# HKCV5.net
KiCad netlist of a schematic drawn in EAGLE
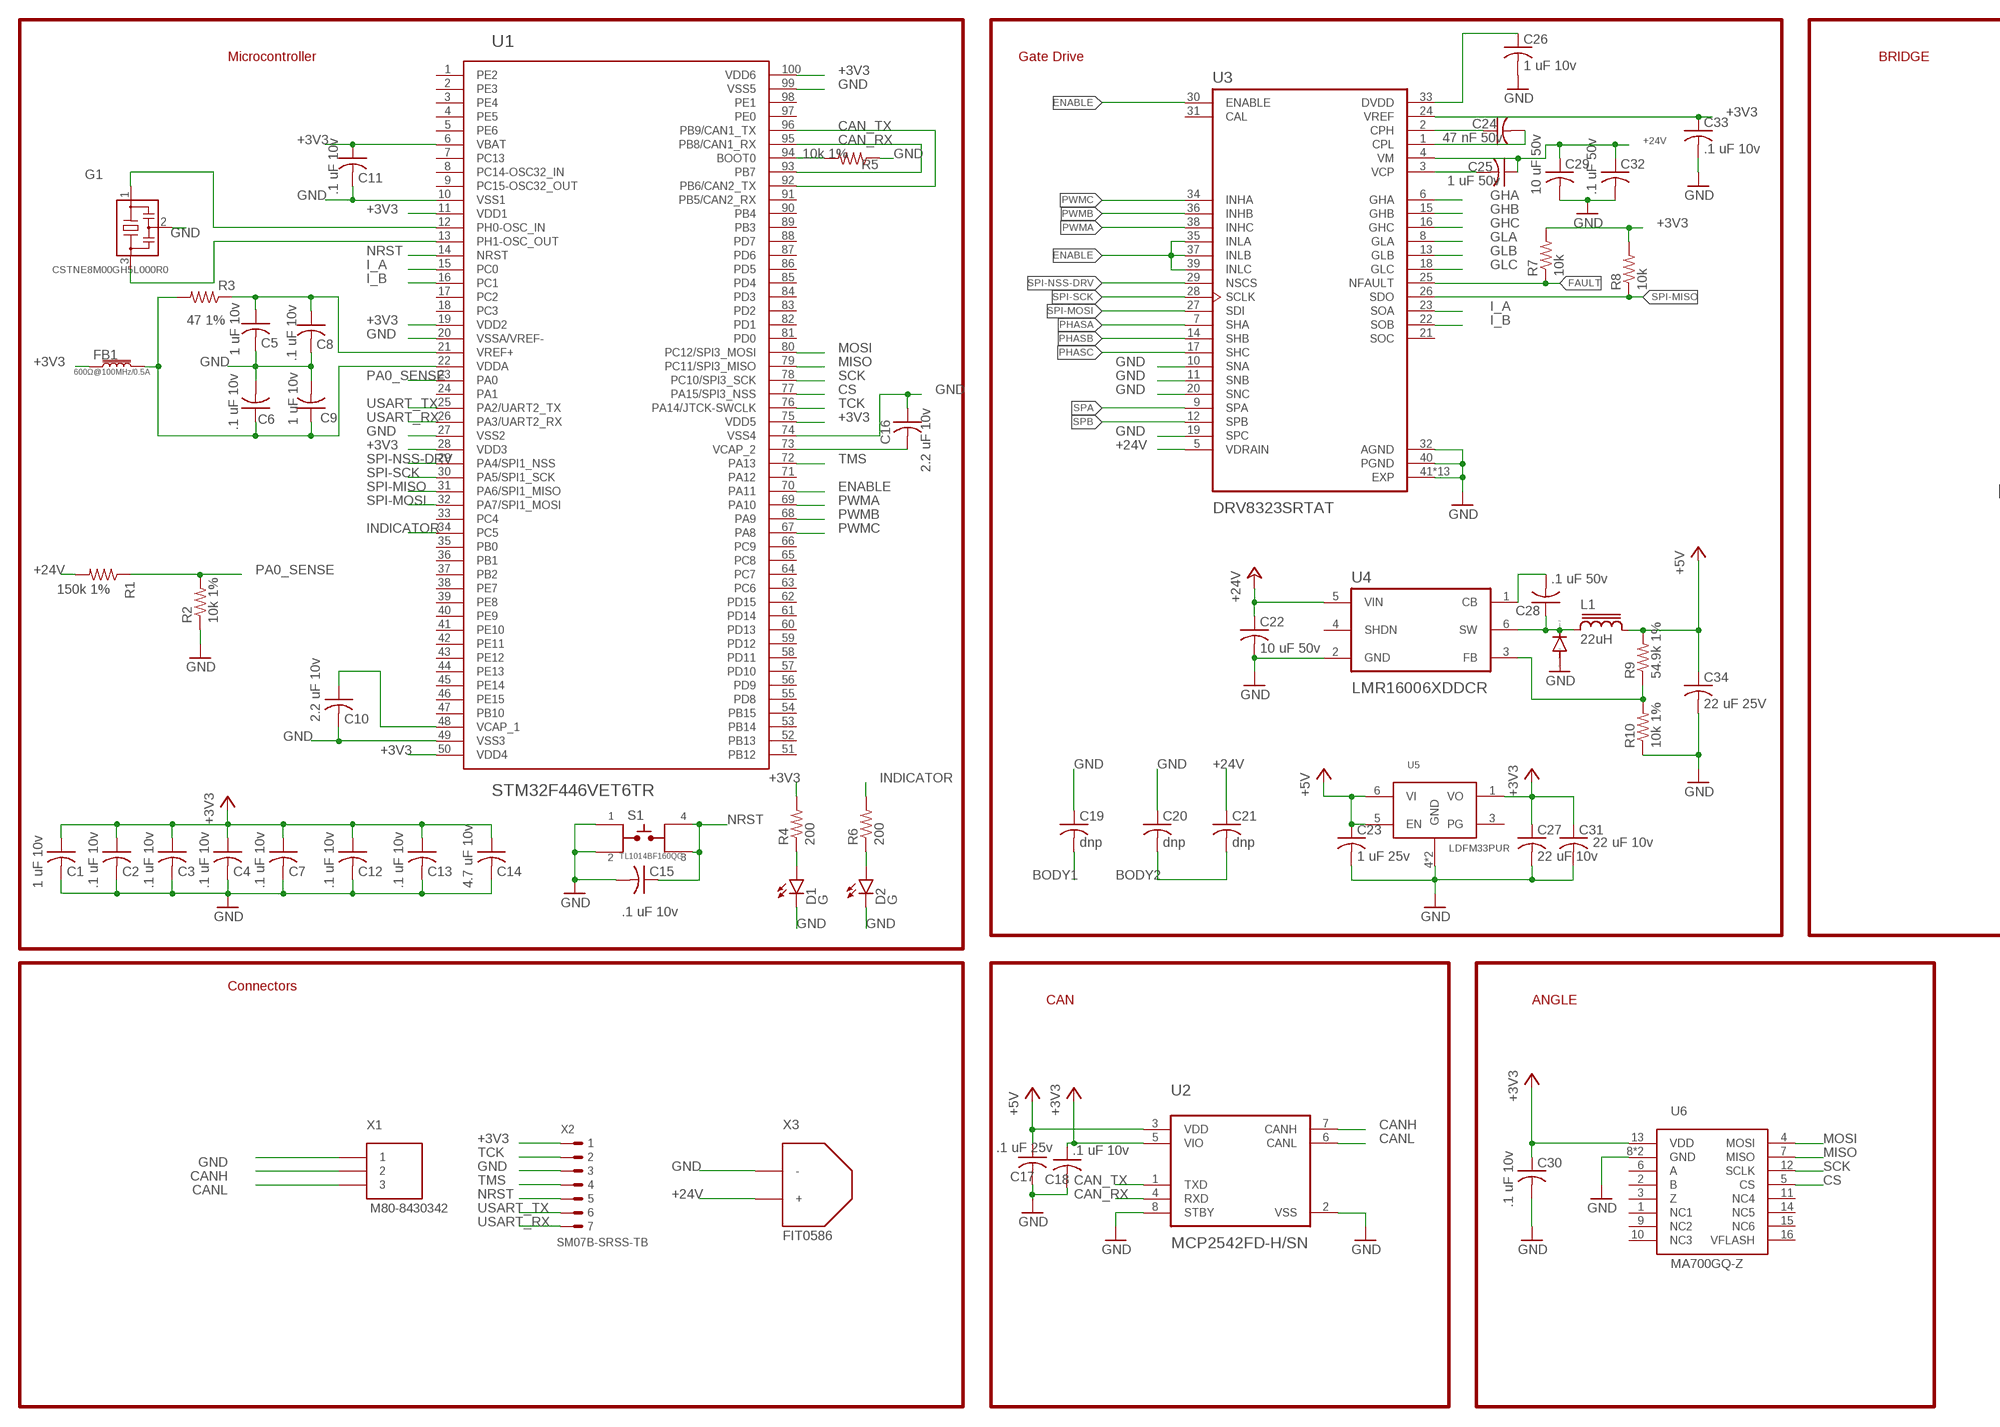
[diagram p0: schematic, sheet 1, part 1 of 2]
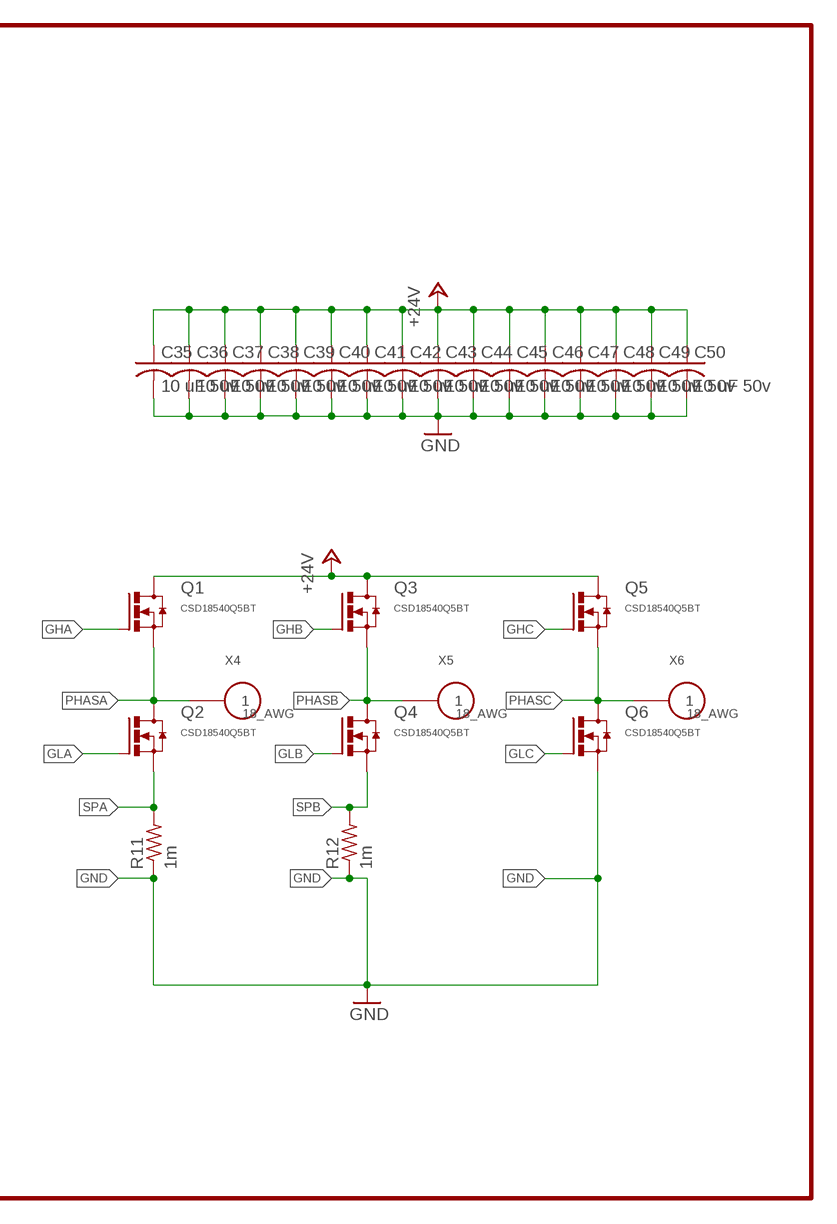
[diagram p1: schematic, sheet 1, part 2 of 2]

(export (version "E")
  (design (tool "Eeschema 10.0.6"))
  (components
    (comp (ref "C1")
      (value "1 uF 10v")
      (footprint "eagle-import:C0402K")
      (libsource (lib "eagle-import") (part "C-USC0402K"))
    )
    (comp (ref "C2")
      (value ".1 uF 10v")
      (footprint "eagle-import:C0402K")
      (libsource (lib "eagle-import") (part "C-USC0402K"))
    )
    (comp (ref "C3")
      (value ".1 uF 10v")
      (footprint "eagle-import:C0402K")
      (libsource (lib "eagle-import") (part "C-USC0402K"))
    )
    (comp (ref "C4")
      (value ".1 uF 10v")
      (footprint "eagle-import:C0402K")
      (libsource (lib "eagle-import") (part "C-USC0402K"))
    )
    (comp (ref "C5")
      (value "1 uF 10v")
      (footprint "eagle-import:C0402K")
      (libsource (lib "eagle-import") (part "C-USC0402K"))
    )
    (comp (ref "C6")
      (value ".1 uF 10v")
      (footprint "eagle-import:C0402K")
      (libsource (lib "eagle-import") (part "C-USC0402K"))
    )
    (comp (ref "C7")
      (value ".1 uF 10v")
      (footprint "eagle-import:C0402K")
      (libsource (lib "eagle-import") (part "C-USC0402K"))
    )
    (comp (ref "C8")
      (value ".1 uF 10v")
      (footprint "eagle-import:C0402K")
      (libsource (lib "eagle-import") (part "C-USC0402K"))
    )
    (comp (ref "C9")
      (value "1 uF 10v")
      (footprint "eagle-import:C0402K")
      (libsource (lib "eagle-import") (part "C-USC0402K"))
    )
    (comp (ref "C10")
      (value "2.2 uF 10v")
      (footprint "eagle-import:C0402K")
      (libsource (lib "eagle-import") (part "C-USC0402K"))
    )
    (comp (ref "C11")
      (value ".1 uF 10v")
      (footprint "eagle-import:C0402K")
      (libsource (lib "eagle-import") (part "C-USC0402K"))
    )
    (comp (ref "C12")
      (value ".1 uF 10v")
      (footprint "eagle-import:C0402K")
      (libsource (lib "eagle-import") (part "C-USC0402K"))
    )
    (comp (ref "C13")
      (value ".1 uF 10v")
      (footprint "eagle-import:C0402K")
      (libsource (lib "eagle-import") (part "C-USC0402K"))
    )
    (comp (ref "C14")
      (value "4.7 uF 10v")
      (footprint "eagle-import:C0402K")
      (libsource (lib "eagle-import") (part "C-USC0402K"))
    )
    (comp (ref "C15")
      (value ".1 uF 10v")
      (footprint "eagle-import:C0402K")
      (libsource (lib "eagle-import") (part "C-USC0402K"))
    )
    (comp (ref "C16")
      (value "2.2 uF 10v")
      (footprint "eagle-import:C0402K")
      (libsource (lib "eagle-import") (part "C-USC0402K"))
    )
    (comp (ref "C17")
      (value ".1 uF 25v")
      (footprint "eagle-import:C0402K")
      (libsource (lib "eagle-import") (part "C-USC0402K"))
    )
    (comp (ref "C18")
      (value ".1 uF 10v")
      (footprint "eagle-import:C0402K")
      (libsource (lib "eagle-import") (part "C-USC0402K"))
    )
    (comp (ref "C19")
      (value "dnp")
      (footprint "eagle-import:C0402K")
      (libsource (lib "eagle-import") (part "C-USC0402K"))
    )
    (comp (ref "C20")
      (value "dnp")
      (footprint "eagle-import:C0402K")
      (libsource (lib "eagle-import") (part "C-USC0402K"))
    )
    (comp (ref "C21")
      (value "dnp")
      (footprint "eagle-import:C0402K")
      (libsource (lib "eagle-import") (part "C-USC0402K"))
    )
    (comp (ref "C22")
      (value "10 uF 50v")
      (footprint "eagle-import:C1206K")
      (libsource (lib "eagle-import") (part "C-USC1206K"))
    )
    (comp (ref "C23")
      (value "1 uF 25v")
      (footprint "eagle-import:C0402K")
      (libsource (lib "eagle-import") (part "C-USC0402K"))
    )
    (comp (ref "C24")
      (value "47 nF 50v")
      (footprint "eagle-import:C0402K")
      (libsource (lib "eagle-import") (part "C-USC0402K"))
    )
    (comp (ref "C25")
      (value "1 uF 50v")
      (footprint "eagle-import:C0603K")
      (libsource (lib "eagle-import") (part "C-USC0603K"))
    )
    (comp (ref "C26")
      (value "1 uF 10v")
      (footprint "eagle-import:C0402K")
      (libsource (lib "eagle-import") (part "C-USC0402K"))
    )
    (comp (ref "C27")
      (value "22 uF 10v")
      (footprint "eagle-import:C0603K")
      (libsource (lib "eagle-import") (part "C-USC0603K"))
    )
    (comp (ref "C28")
      (value ".1 uF 50v")
      (footprint "eagle-import:C0603K")
      (libsource (lib "eagle-import") (part "C-USC0603K"))
    )
    (comp (ref "C29")
      (value "10 uF 50v")
      (footprint "eagle-import:C1206K")
      (libsource (lib "eagle-import") (part "C-USC1206K"))
    )
    (comp (ref "C30")
      (value ".1 uF 10v")
      (footprint "eagle-import:C0402K")
      (libsource (lib "eagle-import") (part "C-USC0402K"))
    )
    (comp (ref "C31")
      (value "22 uF 10v")
      (footprint "eagle-import:C0603K")
      (libsource (lib "eagle-import") (part "C-USC0603K"))
    )
    (comp (ref "C32")
      (value ".1 uF 50v")
      (footprint "eagle-import:C0603K")
      (libsource (lib "eagle-import") (part "C-USC0603K"))
    )
    (comp (ref "C33")
      (value ".1 uF 10v")
      (footprint "eagle-import:C0402K")
      (libsource (lib "eagle-import") (part "C-USC0402K"))
    )
    (comp (ref "C34")
      (value "22 uF 25V")
      (footprint "eagle-import:C0805K")
      (libsource (lib "eagle-import") (part "C-USC0805K"))
    )
    (comp (ref "C35")
      (value "10 uF 50v")
      (footprint "eagle-import:C1206K")
      (libsource (lib "eagle-import") (part "C-USC1206K"))
    )
    (comp (ref "C36")
      (value "10 uF 50v")
      (footprint "eagle-import:C1206K")
      (libsource (lib "eagle-import") (part "C-USC1206K"))
    )
    (comp (ref "C37")
      (value "10 uF 50v")
      (footprint "eagle-import:C1206K")
      (libsource (lib "eagle-import") (part "C-USC1206K"))
    )
    (comp (ref "C38")
      (value "10 uF 50v")
      (footprint "eagle-import:C1206K")
      (libsource (lib "eagle-import") (part "C-USC1206K"))
    )
    (comp (ref "C39")
      (value "10 uF 50v")
      (footprint "eagle-import:C1206K")
      (libsource (lib "eagle-import") (part "C-USC1206K"))
    )
    (comp (ref "C40")
      (value "10 uF 50v")
      (footprint "eagle-import:C1206K")
      (libsource (lib "eagle-import") (part "C-USC1206K"))
    )
    (comp (ref "C41")
      (value "10 uF 50v")
      (footprint "eagle-import:C1206K")
      (libsource (lib "eagle-import") (part "C-USC1206K"))
    )
    (comp (ref "C42")
      (value "10 uF 50v")
      (footprint "eagle-import:C1206K")
      (libsource (lib "eagle-import") (part "C-USC1206K"))
    )
    (comp (ref "C43")
      (value "10 uF 50v")
      (footprint "eagle-import:C1206K")
      (libsource (lib "eagle-import") (part "C-USC1206K"))
    )
    (comp (ref "C44")
      (value "10 uF 50v")
      (footprint "eagle-import:C1206K")
      (libsource (lib "eagle-import") (part "C-USC1206K"))
    )
    (comp (ref "C45")
      (value "10 uF 50v")
      (footprint "eagle-import:C1206K")
      (libsource (lib "eagle-import") (part "C-USC1206K"))
    )
    (comp (ref "C46")
      (value "10 uF 50v")
      (footprint "eagle-import:C1206K")
      (libsource (lib "eagle-import") (part "C-USC1206K"))
    )
    (comp (ref "C47")
      (value "10 uF 50v")
      (footprint "eagle-import:C1206K")
      (libsource (lib "eagle-import") (part "C-USC1206K"))
    )
    (comp (ref "C48")
      (value "10 uF 50v")
      (footprint "eagle-import:C1206K")
      (libsource (lib "eagle-import") (part "C-USC1206K"))
    )
    (comp (ref "C49")
      (value "10 uF 50v")
      (footprint "eagle-import:C1206K")
      (libsource (lib "eagle-import") (part "C-USC1206K"))
    )
    (comp (ref "C50")
      (value "10 uF 50v")
      (footprint "eagle-import:C1206K")
      (libsource (lib "eagle-import") (part "C-USC1206K"))
    )
    (comp (ref "D1")
      (value "G")
      (footprint "eagle-import:LED-0603")
      (libsource (lib "eagle-import") (part "LED0603"))
    )
    (comp (ref "D2")
      (value "G")
      (footprint "eagle-import:LED-0603")
      (libsource (lib "eagle-import") (part "LED0603"))
    )
    (comp (ref "D3")
      (value "500 mA 60v")
      (footprint "eagle-import:SOD123")
      (libsource (lib "eagle-import") (part "DIODE-SOD123"))
    )
    (comp (ref "FB1")
      (value "600Ω@100MHz/0.5A")
      (footprint "eagle-import:0603")
      (libsource (lib "eagle-import") (part "FERRITE_BEAD-0603"))
    )
    (comp (ref "G1")
      (value "CSTNE8M00GH5L000R0")
      (footprint "eagle-import:CSTCE")
      (libsource (lib "eagle-import") (part "CSTNE8M00GH5L000R0"))
    )
    (comp (ref "L1")
      (value "22uH")
      (footprint "eagle-import:SDR0302")
      (libsource (lib "eagle-import") (part "SDR0302"))
    )
    (comp (ref "Q1")
      (value "CSD18540Q5BT")
      (footprint "eagle-import:8-POWERTDFN")
      (libsource (lib "eagle-import") (part "CSD18540Q5BT"))
    )
    (comp (ref "Q2")
      (value "CSD18540Q5BT")
      (footprint "eagle-import:8-POWERTDFN")
      (libsource (lib "eagle-import") (part "CSD18540Q5BT"))
    )
    (comp (ref "Q3")
      (value "CSD18540Q5BT")
      (footprint "eagle-import:8-POWERTDFN")
      (libsource (lib "eagle-import") (part "CSD18540Q5BT"))
    )
    (comp (ref "Q4")
      (value "CSD18540Q5BT")
      (footprint "eagle-import:8-POWERTDFN")
      (libsource (lib "eagle-import") (part "CSD18540Q5BT"))
    )
    (comp (ref "Q5")
      (value "CSD18540Q5BT")
      (footprint "eagle-import:8-POWERTDFN")
      (libsource (lib "eagle-import") (part "CSD18540Q5BT"))
    )
    (comp (ref "Q6")
      (value "CSD18540Q5BT")
      (footprint "eagle-import:8-POWERTDFN")
      (libsource (lib "eagle-import") (part "CSD18540Q5BT"))
    )
    (comp (ref "R1")
      (value "150k 1%")
      (footprint "eagle-import:R0402")
      (libsource (lib "eagle-import") (part "R-US_R0402"))
    )
    (comp (ref "R2")
      (value "10k 1%")
      (footprint "eagle-import:R0402")
      (libsource (lib "eagle-import") (part "R-US_R0402"))
    )
    (comp (ref "R3")
      (value "47 1%")
      (footprint "eagle-import:R0402")
      (libsource (lib "eagle-import") (part "R-US_R0402"))
    )
    (comp (ref "R4")
      (value "200")
      (footprint "eagle-import:R0402")
      (libsource (lib "eagle-import") (part "R-US_R0402"))
    )
    (comp (ref "R5")
      (value "10k 1%")
      (footprint "eagle-import:R0402")
      (libsource (lib "eagle-import") (part "R-US_R0402"))
    )
    (comp (ref "R6")
      (value "200")
      (footprint "eagle-import:R0402")
      (libsource (lib "eagle-import") (part "R-US_R0402"))
    )
    (comp (ref "R7")
      (value "10k")
      (footprint "eagle-import:R0402")
      (libsource (lib "eagle-import") (part "R-US_R0402"))
    )
    (comp (ref "R8")
      (value "10k")
      (footprint "eagle-import:R0402")
      (libsource (lib "eagle-import") (part "R-US_R0402"))
    )
    (comp (ref "R9")
      (value "54.9k 1%")
      (footprint "eagle-import:R0402")
      (libsource (lib "eagle-import") (part "R-US_R0402"))
    )
    (comp (ref "R10")
      (value "10k 1%")
      (footprint "eagle-import:R0402")
      (libsource (lib "eagle-import") (part "R-US_R0402"))
    )
    (comp (ref "R11")
      (value "1m")
      (footprint "eagle-import:R1210")
      (libsource (lib "eagle-import") (part "R-US_R1210"))
    )
    (comp (ref "R12")
      (value "1m")
      (footprint "eagle-import:R1210")
      (libsource (lib "eagle-import") (part "R-US_R1210"))
    )
    (comp (ref "S1")
      (value "TL1014BF160QG")
      (footprint "eagle-import:TL1014")
      (libsource (lib "eagle-import") (part "TL1014BF160QG"))
    )
    (comp (ref "U1")
      (value "STM32F446VET6TR")
      (footprint "eagle-import:LQFP100")
      (libsource (lib "eagle-import") (part "STM32F446VET6TR"))
    )
    (comp (ref "U2")
      (value "MCP2542FD-H/SN")
      (footprint "eagle-import:8-LEADSOIC")
      (libsource (lib "eagle-import") (part "MCP2542FD-H/SN"))
    )
    (comp (ref "U3")
      (value "DRV8323SRTAT")
      (footprint "eagle-import:RTA-PACKAGE")
      (libsource (lib "eagle-import") (part "DRV8323SRTAT"))
    )
    (comp (ref "U4")
      (value "LMR16006XDDCR")
      (footprint "eagle-import:SOT-23-6-THIN")
      (libsource (lib "eagle-import") (part "LMR16006XDDCR"))
    )
    (comp (ref "U5")
      (value "LDFM33PUR")
      (footprint "eagle-import:DFN6-3X3")
      (libsource (lib "eagle-import") (part "LDFM33PUR"))
    )
    (comp (ref "U6")
      (value "MA700GQ-Z")
      (footprint "eagle-import:QFN16")
      (libsource (lib "eagle-import") (part "MA700GQ-Z"))
    )
    (comp (ref "X1")
      (value "M80-8430342")
      (footprint "eagle-import:M80-8430342")
      (libsource (lib "eagle-import") (part "M80-3-PIN"))
    )
    (comp (ref "X2")
      (value "SM07B-SRSS-TB")
      (footprint "eagle-import:SM07B-SRSS-TB")
      (libsource (lib "eagle-import") (part "SM07B-SRSS-TB"))
    )
    (comp (ref "X3")
      (value "FIT0586")
      (footprint "eagle-import:XT30")
      (libsource (lib "eagle-import") (part "FIT0586"))
    )
    (comp (ref "X4")
      (value "18_AWG")
      (footprint "eagle-import:18_AWG_PAD")
      (libsource (lib "eagle-import") (part "18_AWG_PADSINGLE"))
    )
    (comp (ref "X5")
      (value "18_AWG")
      (footprint "eagle-import:18_AWG_PAD")
      (libsource (lib "eagle-import") (part "18_AWG_PADSINGLE"))
    )
    (comp (ref "X6")
      (value "18_AWG")
      (footprint "eagle-import:18_AWG_PAD")
      (libsource (lib "eagle-import") (part "18_AWG_PADSINGLE"))
    )
  )
  (nets
    (net (code "1") (name "+3V3") (class "Default")
      (node (ref "C1") (pin "1") (pinfunction "1_1") (pintype "passive"))
      (node (ref "C11") (pin "1") (pinfunction "1_1") (pintype "passive"))
      (node (ref "C12") (pin "1") (pinfunction "1_1") (pintype "passive"))
      (node (ref "C13") (pin "1") (pinfunction "1_1") (pintype "passive"))
      (node (ref "C14") (pin "1") (pinfunction "1_1") (pintype "passive"))
      (node (ref "C18") (pin "1") (pinfunction "1_1") (pintype "passive"))
      (node (ref "C2") (pin "1") (pinfunction "1_1") (pintype "passive"))
      (node (ref "C27") (pin "1") (pinfunction "1_1") (pintype "passive"))
      (node (ref "C3") (pin "1") (pinfunction "1_1") (pintype "passive"))
      (node (ref "C30") (pin "1") (pinfunction "1_1") (pintype "passive"))
      (node (ref "C31") (pin "1") (pinfunction "1_1") (pintype "passive"))
      (node (ref "C33") (pin "1") (pinfunction "1_1") (pintype "passive"))
      (node (ref "C4") (pin "1") (pinfunction "1_1") (pintype "passive"))
      (node (ref "C7") (pin "1") (pinfunction "1_1") (pintype "passive"))
      (node (ref "FB1") (pin "1") (pinfunction "1_1") (pintype "passive"))
      (node (ref "R4") (pin "2") (pinfunction "2_2") (pintype "passive"))
      (node (ref "R7") (pin "2") (pinfunction "2_2") (pintype "passive"))
      (node (ref "R8") (pin "2") (pinfunction "2_2") (pintype "passive"))
      (node (ref "U1") (pin "100") (pinfunction "VDD6_100") (pintype "bidirectional"))
      (node (ref "U1") (pin "11") (pinfunction "VDD1_11") (pintype "bidirectional"))
      (node (ref "U1") (pin "19") (pinfunction "VDD2_19") (pintype "bidirectional"))
      (node (ref "U1") (pin "28") (pinfunction "VDD3_28") (pintype "bidirectional"))
      (node (ref "U1") (pin "50") (pinfunction "VDD4_50") (pintype "bidirectional"))
      (node (ref "U1") (pin "6") (pinfunction "VBAT_6") (pintype "bidirectional"))
      (node (ref "U1") (pin "75") (pinfunction "VDD5_75") (pintype "bidirectional"))
      (node (ref "U2") (pin "5") (pinfunction "VIO_5") (pintype "power_in"))
      (node (ref "U3") (pin "24") (pinfunction "VREF_24") (pintype "power_in"))
      (node (ref "U5") (pin "1") (pinfunction "VO_1") (pintype "bidirectional"))
      (node (ref "U6") (pin "13") (pinfunction "VDD_13") (pintype "bidirectional"))
      (node (ref "X2") (pin "1") (pinfunction "1_1") (pintype "passive"))
    )
    (net (code "2") (name "+5V") (class "Default")
      (node (ref "C17") (pin "1") (pinfunction "1_1") (pintype "passive"))
      (node (ref "C23") (pin "1") (pinfunction "1_1") (pintype "passive"))
      (node (ref "C34") (pin "1") (pinfunction "1_1") (pintype "passive"))
      (node (ref "L1") (pin "2") (pinfunction "2_2") (pintype "passive"))
      (node (ref "R9") (pin "2") (pinfunction "2_2") (pintype "passive"))
      (node (ref "U2") (pin "3") (pinfunction "VDD_3") (pintype "power_in"))
      (node (ref "U5") (pin "5") (pinfunction "EN_5") (pintype "bidirectional"))
      (node (ref "U5") (pin "6") (pinfunction "VI_6") (pintype "bidirectional"))
    )
    (net (code "3") (name "+24V") (class "Default")
      (node (ref "C21") (pin "1") (pinfunction "1_1") (pintype "passive"))
      (node (ref "C22") (pin "1") (pinfunction "1_1") (pintype "passive"))
      (node (ref "C25") (pin "1") (pinfunction "1_1") (pintype "passive"))
      (node (ref "C29") (pin "1") (pinfunction "1_1") (pintype "passive"))
      (node (ref "C32") (pin "1") (pinfunction "1_1") (pintype "passive"))
      (node (ref "C35") (pin "1") (pinfunction "1_1") (pintype "passive"))
      (node (ref "C36") (pin "1") (pinfunction "1_1") (pintype "passive"))
      (node (ref "C37") (pin "1") (pinfunction "1_1") (pintype "passive"))
      (node (ref "C38") (pin "1") (pinfunction "1_1") (pintype "passive"))
      (node (ref "C39") (pin "1") (pinfunction "1_1") (pintype "passive"))
      (node (ref "C40") (pin "1") (pinfunction "1_1") (pintype "passive"))
      (node (ref "C41") (pin "1") (pinfunction "1_1") (pintype "passive"))
      (node (ref "C42") (pin "1") (pinfunction "1_1") (pintype "passive"))
      (node (ref "C43") (pin "1") (pinfunction "1_1") (pintype "passive"))
      (node (ref "C44") (pin "1") (pinfunction "1_1") (pintype "passive"))
      (node (ref "C45") (pin "1") (pinfunction "1_1") (pintype "passive"))
      (node (ref "C46") (pin "1") (pinfunction "1_1") (pintype "passive"))
      (node (ref "C47") (pin "1") (pinfunction "1_1") (pintype "passive"))
      (node (ref "C48") (pin "1") (pinfunction "1_1") (pintype "passive"))
      (node (ref "C49") (pin "1") (pinfunction "1_1") (pintype "passive"))
      (node (ref "C50") (pin "1") (pinfunction "1_1") (pintype "passive"))
      (node (ref "Q1") (pin "5_1") (pinfunction "D_5_1") (pintype "passive"))
      (node (ref "Q1") (pin "5_10") (pinfunction "D_5_10") (pintype "passive"))
      (node (ref "Q1") (pin "5_11") (pinfunction "D_5_11") (pintype "passive"))
      (node (ref "Q1") (pin "5_12") (pinfunction "D_5_12") (pintype "passive"))
      (node (ref "Q1") (pin "5_13") (pinfunction "D_5_13") (pintype "passive"))
      (node (ref "Q1") (pin "5_14") (pinfunction "D_5_14") (pintype "passive"))
      (node (ref "Q1") (pin "5_15") (pinfunction "D_5_15") (pintype "passive"))
      (node (ref "Q1") (pin "5_16") (pinfunction "D_5_16") (pintype "passive"))
      (node (ref "Q1") (pin "5_17") (pinfunction "D_5_17") (pintype "passive"))
      (node (ref "Q1") (pin "5_18") (pinfunction "D_5_18") (pintype "passive"))
      (node (ref "Q1") (pin "5_19") (pinfunction "D_5_19") (pintype "passive"))
      (node (ref "Q1") (pin "5_2") (pinfunction "D_5_2") (pintype "passive"))
      (node (ref "Q1") (pin "5_20") (pinfunction "D_5_20") (pintype "passive"))
      (node (ref "Q1") (pin "5_21") (pinfunction "D_5_21") (pintype "passive"))
      (node (ref "Q1") (pin "5_22") (pinfunction "D_5_22") (pintype "passive"))
      (node (ref "Q1") (pin "5_23") (pinfunction "D_5_23") (pintype "passive"))
      (node (ref "Q1") (pin "5_24") (pinfunction "D_5_24") (pintype "passive"))
      (node (ref "Q1") (pin "5_25") (pinfunction "D_5_25") (pintype "passive"))
      (node (ref "Q1") (pin "5_26") (pinfunction "D_5_26") (pintype "passive"))
      (node (ref "Q1") (pin "5_27") (pinfunction "D_5_27") (pintype "passive"))
      (node (ref "Q1") (pin "5_28") (pinfunction "D_5_28") (pintype "passive"))
      (node (ref "Q1") (pin "5_29") (pinfunction "D_5_29") (pintype "passive"))
      (node (ref "Q1") (pin "5_3") (pinfunction "D_5_3") (pintype "passive"))
      (node (ref "Q1") (pin "5_30") (pinfunction "D_5_30") (pintype "passive"))
      (node (ref "Q1") (pin "5_4") (pinfunction "D_5_4") (pintype "passive"))
      (node (ref "Q1") (pin "5_5") (pinfunction "D_5_5") (pintype "passive"))
      (node (ref "Q1") (pin "5_6") (pinfunction "D_5_6") (pintype "passive"))
      (node (ref "Q1") (pin "5_7") (pinfunction "D_5_7") (pintype "passive"))
      (node (ref "Q1") (pin "5_8") (pinfunction "D_5_8") (pintype "passive"))
      (node (ref "Q1") (pin "5_9") (pinfunction "D_5_9") (pintype "passive"))
      (node (ref "Q3") (pin "5_1") (pinfunction "D_5_1") (pintype "passive"))
      (node (ref "Q3") (pin "5_10") (pinfunction "D_5_10") (pintype "passive"))
      (node (ref "Q3") (pin "5_11") (pinfunction "D_5_11") (pintype "passive"))
      (node (ref "Q3") (pin "5_12") (pinfunction "D_5_12") (pintype "passive"))
      (node (ref "Q3") (pin "5_13") (pinfunction "D_5_13") (pintype "passive"))
      (node (ref "Q3") (pin "5_14") (pinfunction "D_5_14") (pintype "passive"))
      (node (ref "Q3") (pin "5_15") (pinfunction "D_5_15") (pintype "passive"))
      (node (ref "Q3") (pin "5_16") (pinfunction "D_5_16") (pintype "passive"))
      (node (ref "Q3") (pin "5_17") (pinfunction "D_5_17") (pintype "passive"))
      (node (ref "Q3") (pin "5_18") (pinfunction "D_5_18") (pintype "passive"))
      (node (ref "Q3") (pin "5_19") (pinfunction "D_5_19") (pintype "passive"))
      (node (ref "Q3") (pin "5_2") (pinfunction "D_5_2") (pintype "passive"))
      (node (ref "Q3") (pin "5_20") (pinfunction "D_5_20") (pintype "passive"))
      (node (ref "Q3") (pin "5_21") (pinfunction "D_5_21") (pintype "passive"))
      (node (ref "Q3") (pin "5_22") (pinfunction "D_5_22") (pintype "passive"))
      (node (ref "Q3") (pin "5_23") (pinfunction "D_5_23") (pintype "passive"))
      (node (ref "Q3") (pin "5_24") (pinfunction "D_5_24") (pintype "passive"))
      (node (ref "Q3") (pin "5_25") (pinfunction "D_5_25") (pintype "passive"))
      (node (ref "Q3") (pin "5_26") (pinfunction "D_5_26") (pintype "passive"))
      (node (ref "Q3") (pin "5_27") (pinfunction "D_5_27") (pintype "passive"))
      (node (ref "Q3") (pin "5_28") (pinfunction "D_5_28") (pintype "passive"))
      (node (ref "Q3") (pin "5_29") (pinfunction "D_5_29") (pintype "passive"))
      (node (ref "Q3") (pin "5_3") (pinfunction "D_5_3") (pintype "passive"))
      (node (ref "Q3") (pin "5_30") (pinfunction "D_5_30") (pintype "passive"))
      (node (ref "Q3") (pin "5_4") (pinfunction "D_5_4") (pintype "passive"))
      (node (ref "Q3") (pin "5_5") (pinfunction "D_5_5") (pintype "passive"))
      (node (ref "Q3") (pin "5_6") (pinfunction "D_5_6") (pintype "passive"))
      (node (ref "Q3") (pin "5_7") (pinfunction "D_5_7") (pintype "passive"))
      (node (ref "Q3") (pin "5_8") (pinfunction "D_5_8") (pintype "passive"))
      (node (ref "Q3") (pin "5_9") (pinfunction "D_5_9") (pintype "passive"))
      (node (ref "Q5") (pin "5_1") (pinfunction "D_5_1") (pintype "passive"))
      (node (ref "Q5") (pin "5_10") (pinfunction "D_5_10") (pintype "passive"))
      (node (ref "Q5") (pin "5_11") (pinfunction "D_5_11") (pintype "passive"))
      (node (ref "Q5") (pin "5_12") (pinfunction "D_5_12") (pintype "passive"))
      (node (ref "Q5") (pin "5_13") (pinfunction "D_5_13") (pintype "passive"))
      (node (ref "Q5") (pin "5_14") (pinfunction "D_5_14") (pintype "passive"))
      (node (ref "Q5") (pin "5_15") (pinfunction "D_5_15") (pintype "passive"))
      (node (ref "Q5") (pin "5_16") (pinfunction "D_5_16") (pintype "passive"))
      (node (ref "Q5") (pin "5_17") (pinfunction "D_5_17") (pintype "passive"))
      (node (ref "Q5") (pin "5_18") (pinfunction "D_5_18") (pintype "passive"))
      (node (ref "Q5") (pin "5_19") (pinfunction "D_5_19") (pintype "passive"))
      (node (ref "Q5") (pin "5_2") (pinfunction "D_5_2") (pintype "passive"))
      (node (ref "Q5") (pin "5_20") (pinfunction "D_5_20") (pintype "passive"))
      (node (ref "Q5") (pin "5_21") (pinfunction "D_5_21") (pintype "passive"))
      (node (ref "Q5") (pin "5_22") (pinfunction "D_5_22") (pintype "passive"))
      (node (ref "Q5") (pin "5_23") (pinfunction "D_5_23") (pintype "passive"))
      (node (ref "Q5") (pin "5_24") (pinfunction "D_5_24") (pintype "passive"))
      (node (ref "Q5") (pin "5_25") (pinfunction "D_5_25") (pintype "passive"))
      (node (ref "Q5") (pin "5_26") (pinfunction "D_5_26") (pintype "passive"))
      (node (ref "Q5") (pin "5_27") (pinfunction "D_5_27") (pintype "passive"))
      (node (ref "Q5") (pin "5_28") (pinfunction "D_5_28") (pintype "passive"))
      (node (ref "Q5") (pin "5_29") (pinfunction "D_5_29") (pintype "passive"))
      (node (ref "Q5") (pin "5_3") (pinfunction "D_5_3") (pintype "passive"))
      (node (ref "Q5") (pin "5_30") (pinfunction "D_5_30") (pintype "passive"))
      (node (ref "Q5") (pin "5_4") (pinfunction "D_5_4") (pintype "passive"))
      (node (ref "Q5") (pin "5_5") (pinfunction "D_5_5") (pintype "passive"))
      (node (ref "Q5") (pin "5_6") (pinfunction "D_5_6") (pintype "passive"))
      (node (ref "Q5") (pin "5_7") (pinfunction "D_5_7") (pintype "passive"))
      (node (ref "Q5") (pin "5_8") (pinfunction "D_5_8") (pintype "passive"))
      (node (ref "Q5") (pin "5_9") (pinfunction "D_5_9") (pintype "passive"))
      (node (ref "R1") (pin "2") (pinfunction "2_2") (pintype "passive"))
      (node (ref "U3") (pin "4") (pinfunction "VM_4") (pintype "power_in"))
      (node (ref "U3") (pin "5") (pinfunction "VDRAIN_5") (pintype "input"))
      (node (ref "U4") (pin "5") (pinfunction "VIN_5") (pintype "input"))
      (node (ref "X3") (pin "+") (pinfunction "+_+") (pintype "bidirectional"))
    )
    (net (code "4") (name "/BODY1") (class "Default")
      (node (ref "C19") (pin "2") (pinfunction "2_2") (pintype "passive"))
    )
    (net (code "5") (name "/BODY2") (class "Default")
      (node (ref "C20") (pin "2") (pinfunction "2_2") (pintype "passive"))
      (node (ref "C21") (pin "2") (pinfunction "2_2") (pintype "passive"))
    )
    (net (code "6") (name "/CANH") (class "Default")
      (node (ref "U2") (pin "7") (pinfunction "CANH_7") (pintype "bidirectional"))
      (node (ref "X1") (pin "2") (pinfunction "2_2") (pintype "bidirectional"))
    )
    (net (code "7") (name "/CANL") (class "Default")
      (node (ref "U2") (pin "6") (pinfunction "CANL_6") (pintype "bidirectional"))
      (node (ref "X1") (pin "3") (pinfunction "3_3") (pintype "bidirectional"))
    )
    (net (code "8") (name "/CAN_RX") (class "Default")
      (node (ref "U1") (pin "93") (pinfunction "PB7_93") (pintype "bidirectional"))
      (node (ref "U1") (pin "95") (pinfunction "PB8/CAN1_RX_95") (pintype "bidirectional"))
      (node (ref "U2") (pin "4") (pinfunction "RXD_4") (pintype "output"))
    )
    (net (code "9") (name "/CAN_TX") (class "Default")
      (node (ref "U1") (pin "92") (pinfunction "PB6/CAN2_TX_92") (pintype "bidirectional"))
      (node (ref "U1") (pin "96") (pinfunction "PB9/CAN1_TX_96") (pintype "bidirectional"))
      (node (ref "U2") (pin "1") (pinfunction "TXD_1") (pintype "input"))
    )
    (net (code "10") (name "/CS") (class "Default")
      (node (ref "U1") (pin "77") (pinfunction "PA15/SPI3_NSS_77") (pintype "bidirectional"))
      (node (ref "U6") (pin "5") (pinfunction "CS_5") (pintype "bidirectional"))
    )
    (net (code "11") (name "/INDICATOR") (class "Default")
      (node (ref "R6") (pin "2") (pinfunction "2_2") (pintype "passive"))
      (node (ref "U1") (pin "34") (pinfunction "PC5_34") (pintype "bidirectional"))
    )
    (net (code "12") (name "/I_A") (class "Default")
      (node (ref "U1") (pin "15") (pinfunction "PC0_15") (pintype "bidirectional"))
      (node (ref "U3") (pin "23") (pinfunction "SOA_23") (pintype "output"))
    )
    (net (code "13") (name "/I_B") (class "Default")
      (node (ref "U1") (pin "16") (pinfunction "PC1_16") (pintype "bidirectional"))
      (node (ref "U3") (pin "22") (pinfunction "SOB_22") (pintype "output"))
    )
    (net (code "14") (name "/MISO") (class "Default")
      (node (ref "U1") (pin "79") (pinfunction "PC11/SPI3_MISO_79") (pintype "bidirectional"))
      (node (ref "U6") (pin "7") (pinfunction "MISO_7") (pintype "bidirectional"))
    )
    (net (code "15") (name "/MOSI") (class "Default")
      (node (ref "U1") (pin "80") (pinfunction "PC12/SPI3_MOSI_80") (pintype "bidirectional"))
      (node (ref "U6") (pin "4") (pinfunction "MOSI_4") (pintype "bidirectional"))
    )
    (net (code "16") (name "/NRST") (class "Default")
      (node (ref "C15") (pin "1") (pinfunction "1_1") (pintype "passive"))
      (node (ref "S1") (pin "3") (pinfunction "3_3") (pintype "bidirectional"))
      (node (ref "S1") (pin "4") (pinfunction "4_4") (pintype "bidirectional"))
      (node (ref "U1") (pin "14") (pinfunction "NRST_14") (pintype "bidirectional"))
      (node (ref "X2") (pin "5") (pinfunction "5_5") (pintype "passive"))
    )
    (net (code "17") (name "/PA0_SENSE") (class "Default")
      (node (ref "R1") (pin "1") (pinfunction "1_1") (pintype "passive"))
      (node (ref "R2") (pin "2") (pinfunction "2_2") (pintype "passive"))
      (node (ref "U1") (pin "23") (pinfunction "PA0_23") (pintype "bidirectional"))
    )
    (net (code "18") (name "/SCK") (class "Default")
      (node (ref "U1") (pin "78") (pinfunction "PC10/SPI3_SCK_78") (pintype "bidirectional"))
      (node (ref "U6") (pin "12") (pinfunction "SCLK_12") (pintype "bidirectional"))
    )
    (net (code "19") (name "/TCK") (class "Default")
      (node (ref "U1") (pin "76") (pinfunction "PA14/JTCK-SWCLK_76") (pintype "bidirectional"))
      (node (ref "X2") (pin "2") (pinfunction "2_2") (pintype "passive"))
    )
    (net (code "20") (name "/TMS") (class "Default")
      (node (ref "U1") (pin "72") (pinfunction "PA13_72") (pintype "bidirectional"))
      (node (ref "X2") (pin "4") (pinfunction "4_4") (pintype "passive"))
    )
    (net (code "21") (name "/USART_RX") (class "Default")
      (node (ref "U1") (pin "26") (pinfunction "PA3/UART2_RX_26") (pintype "bidirectional"))
      (node (ref "X2") (pin "7") (pinfunction "7_7") (pintype "passive"))
    )
    (net (code "22") (name "/USART_TX") (class "Default")
      (node (ref "U1") (pin "25") (pinfunction "PA2/UART2_TX_25") (pintype "bidirectional"))
      (node (ref "X2") (pin "6") (pinfunction "6_6") (pintype "passive"))
    )
    (net (code "23") (name "ENABLE") (class "Default")
      (node (ref "U1") (pin "70") (pinfunction "PA11_70") (pintype "bidirectional"))
      (node (ref "U3") (pin "30") (pinfunction "ENABLE_30") (pintype "input"))
      (node (ref "U3") (pin "35") (pinfunction "INLA_35") (pintype "input"))
      (node (ref "U3") (pin "37") (pinfunction "INLB_37") (pintype "input"))
      (node (ref "U3") (pin "39") (pinfunction "INLC_39") (pintype "input"))
    )
    (net (code "24") (name "FAULT") (class "Default")
      (node (ref "R7") (pin "1") (pinfunction "1_1") (pintype "passive"))
      (node (ref "U3") (pin "25") (pinfunction "NFAULT_25") (pintype "output"))
    )
    (net (code "25") (name "GHA") (class "Default")
      (node (ref "Q1") (pin "4") (pinfunction "G_4") (pintype "passive"))
      (node (ref "U3") (pin "6") (pinfunction "GHA_6") (pintype "output"))
    )
    (net (code "26") (name "GHB") (class "Default")
      (node (ref "Q3") (pin "4") (pinfunction "G_4") (pintype "passive"))
      (node (ref "U3") (pin "15") (pinfunction "GHB_15") (pintype "output"))
    )
    (net (code "27") (name "GHC") (class "Default")
      (node (ref "Q5") (pin "4") (pinfunction "G_4") (pintype "passive"))
      (node (ref "U3") (pin "16") (pinfunction "GHC_16") (pintype "output"))
    )
    (net (code "28") (name "GLA") (class "Default")
      (node (ref "Q2") (pin "4") (pinfunction "G_4") (pintype "passive"))
      (node (ref "U3") (pin "8") (pinfunction "GLA_8") (pintype "output"))
    )
    (net (code "29") (name "GLB") (class "Default")
      (node (ref "Q4") (pin "4") (pinfunction "G_4") (pintype "passive"))
      (node (ref "U3") (pin "13") (pinfunction "GLB_13") (pintype "output"))
    )
    (net (code "30") (name "GLC") (class "Default")
      (node (ref "Q6") (pin "4") (pinfunction "G_4") (pintype "passive"))
      (node (ref "U3") (pin "18") (pinfunction "GLC_18") (pintype "output"))
    )
    (net (code "31") (name "GND") (class "Default")
      (node (ref "C1") (pin "2") (pinfunction "2_2") (pintype "passive"))
      (node (ref "C10") (pin "2") (pinfunction "2_2") (pintype "passive"))
      (node (ref "C11") (pin "2") (pinfunction "2_2") (pintype "passive"))
      (node (ref "C12") (pin "2") (pinfunction "2_2") (pintype "passive"))
      (node (ref "C13") (pin "2") (pinfunction "2_2") (pintype "passive"))
      (node (ref "C14") (pin "2") (pinfunction "2_2") (pintype "passive"))
      (node (ref "C15") (pin "2") (pinfunction "2_2") (pintype "passive"))
      (node (ref "C16") (pin "1") (pinfunction "1_1") (pintype "passive"))
      (node (ref "C17") (pin "2") (pinfunction "2_2") (pintype "passive"))
      (node (ref "C18") (pin "2") (pinfunction "2_2") (pintype "passive"))
      (node (ref "C19") (pin "1") (pinfunction "1_1") (pintype "passive"))
      (node (ref "C2") (pin "2") (pinfunction "2_2") (pintype "passive"))
      (node (ref "C20") (pin "1") (pinfunction "1_1") (pintype "passive"))
      (node (ref "C22") (pin "2") (pinfunction "2_2") (pintype "passive"))
      (node (ref "C23") (pin "2") (pinfunction "2_2") (pintype "passive"))
      (node (ref "C26") (pin "2") (pinfunction "2_2") (pintype "passive"))
      (node (ref "C27") (pin "2") (pinfunction "2_2") (pintype "passive"))
      (node (ref "C29") (pin "2") (pinfunction "2_2") (pintype "passive"))
      (node (ref "C3") (pin "2") (pinfunction "2_2") (pintype "passive"))
      (node (ref "C30") (pin "2") (pinfunction "2_2") (pintype "passive"))
      (node (ref "C31") (pin "2") (pinfunction "2_2") (pintype "passive"))
      (node (ref "C32") (pin "2") (pinfunction "2_2") (pintype "passive"))
      (node (ref "C33") (pin "2") (pinfunction "2_2") (pintype "passive"))
      (node (ref "C34") (pin "2") (pinfunction "2_2") (pintype "passive"))
      (node (ref "C35") (pin "2") (pinfunction "2_2") (pintype "passive"))
      (node (ref "C36") (pin "2") (pinfunction "2_2") (pintype "passive"))
      (node (ref "C37") (pin "2") (pinfunction "2_2") (pintype "passive"))
      (node (ref "C38") (pin "2") (pinfunction "2_2") (pintype "passive"))
      (node (ref "C39") (pin "2") (pinfunction "2_2") (pintype "passive"))
      (node (ref "C4") (pin "2") (pinfunction "2_2") (pintype "passive"))
      (node (ref "C40") (pin "2") (pinfunction "2_2") (pintype "passive"))
      (node (ref "C41") (pin "2") (pinfunction "2_2") (pintype "passive"))
      (node (ref "C42") (pin "2") (pinfunction "2_2") (pintype "passive"))
      (node (ref "C43") (pin "2") (pinfunction "2_2") (pintype "passive"))
      (node (ref "C44") (pin "2") (pinfunction "2_2") (pintype "passive"))
      (node (ref "C45") (pin "2") (pinfunction "2_2") (pintype "passive"))
      (node (ref "C46") (pin "2") (pinfunction "2_2") (pintype "passive"))
      (node (ref "C47") (pin "2") (pinfunction "2_2") (pintype "passive"))
      (node (ref "C48") (pin "2") (pinfunction "2_2") (pintype "passive"))
      (node (ref "C49") (pin "2") (pinfunction "2_2") (pintype "passive"))
      (node (ref "C5") (pin "2") (pinfunction "2_2") (pintype "passive"))
      (node (ref "C50") (pin "2") (pinfunction "2_2") (pintype "passive"))
      (node (ref "C6") (pin "2") (pinfunction "2_2") (pintype "passive"))
      (node (ref "C7") (pin "2") (pinfunction "2_2") (pintype "passive"))
      (node (ref "C8") (pin "2") (pinfunction "2_2") (pintype "passive"))
      (node (ref "C9") (pin "2") (pinfunction "2_2") (pintype "passive"))
      (node (ref "D1") (pin "C") (pinfunction "C_C") (pintype "passive"))
      (node (ref "D2") (pin "C") (pinfunction "C_C") (pintype "passive"))
      (node (ref "D3") (pin "A") (pinfunction "A_A") (pintype "passive"))
      (node (ref "G1") (pin "2") (pinfunction "2_2") (pintype "passive"))
      (node (ref "Q6") (pin "1") (pinfunction "S_1") (pintype "passive"))
      (node (ref "Q6") (pin "2") (pinfunction "S_2") (pintype "passive"))
      (node (ref "Q6") (pin "3") (pinfunction "S_3") (pintype "passive"))
      (node (ref "R10") (pin "1") (pinfunction "1_1") (pintype "passive"))
      (node (ref "R11") (pin "1") (pinfunction "1_1") (pintype "passive"))
      (node (ref "R12") (pin "1") (pinfunction "1_1") (pintype "passive"))
      (node (ref "R2") (pin "1") (pinfunction "1_1") (pintype "passive"))
      (node (ref "R5") (pin "1") (pinfunction "1_1") (pintype "passive"))
      (node (ref "S1") (pin "1") (pinfunction "1_1") (pintype "bidirectional"))
      (node (ref "S1") (pin "2") (pinfunction "2_2") (pintype "bidirectional"))
      (node (ref "U1") (pin "10") (pinfunction "VSS1_10") (pintype "bidirectional"))
      (node (ref "U1") (pin "20") (pinfunction "VSSA/VREF-_20") (pintype "bidirectional"))
      (node (ref "U1") (pin "27") (pinfunction "VSS2_27") (pintype "bidirectional"))
      (node (ref "U1") (pin "49") (pinfunction "VSS3_49") (pintype "bidirectional"))
      (node (ref "U1") (pin "74") (pinfunction "VSS4_74") (pintype "bidirectional"))
      (node (ref "U1") (pin "99") (pinfunction "VSS5_99") (pintype "bidirectional"))
      (node (ref "U2") (pin "2") (pinfunction "VSS_2") (pintype "power_in"))
      (node (ref "U2") (pin "8") (pinfunction "STBY_8") (pintype "input"))
      (node (ref "U3") (pin "10") (pinfunction "SNA_10") (pintype "input"))
      (node (ref "U3") (pin "11") (pinfunction "SNB_11") (pintype "input"))
      (node (ref "U3") (pin "19") (pinfunction "SPC_19") (pintype "input"))
      (node (ref "U3") (pin "20") (pinfunction "SNC_20") (pintype "input"))
      (node (ref "U3") (pin "32") (pinfunction "AGND_32") (pintype "power_in"))
      (node (ref "U3") (pin "40") (pinfunction "PGND_40") (pintype "power_in"))
      (node (ref "U3") (pin "41") (pinfunction "EXP_41") (pintype "power_in"))
      (node (ref "U3") (pin "41_1") (pinfunction "EXP_41_1") (pintype "power_in"))
      (node (ref "U3") (pin "41_10") (pinfunction "EXP_41_10") (pintype "power_in"))
      (node (ref "U3") (pin "41_11") (pinfunction "EXP_41_11") (pintype "power_in"))
      (node (ref "U3") (pin "41_12") (pinfunction "EXP_41_12") (pintype "power_in"))
      (node (ref "U3") (pin "41_2") (pinfunction "EXP_41_2") (pintype "power_in"))
      (node (ref "U3") (pin "41_3") (pinfunction "EXP_41_3") (pintype "power_in"))
      (node (ref "U3") (pin "41_4") (pinfunction "EXP_41_4") (pintype "power_in"))
      (node (ref "U3") (pin "41_5") (pinfunction "EXP_41_5") (pintype "power_in"))
      (node (ref "U3") (pin "41_6") (pinfunction "EXP_41_6") (pintype "power_in"))
      (node (ref "U3") (pin "41_7") (pinfunction "EXP_41_7") (pintype "power_in"))
      (node (ref "U3") (pin "41_8") (pinfunction "EXP_41_8") (pintype "power_in"))
      (node (ref "U3") (pin "41_9") (pinfunction "EXP_41_9") (pintype "power_in"))
      (node (ref "U4") (pin "2") (pinfunction "GND_2") (pintype "power_in"))
      (node (ref "U5") (pin "4") (pinfunction "GND_4") (pintype "bidirectional"))
      (node (ref "U5") (pin "EXP") (pinfunction "GND_EXP") (pintype "bidirectional"))
      (node (ref "U6") (pin "8") (pinfunction "GND_8") (pintype "bidirectional"))
      (node (ref "U6") (pin "TH") (pinfunction "GND_TH") (pintype "bidirectional"))
      (node (ref "X1") (pin "1") (pinfunction "1_1") (pintype "bidirectional"))
      (node (ref "X2") (pin "3") (pinfunction "3_3") (pintype "passive"))
      (node (ref "X3") (pin "-") (pinfunction "-_-") (pintype "bidirectional"))
    )
    (net (code "32") (name "Net-(D1-PadA)") (class "Default")
      (node (ref "D1") (pin "A") (pinfunction "A_A") (pintype "passive"))
      (node (ref "R4") (pin "1") (pinfunction "1_1") (pintype "passive"))
    )
    (net (code "33") (name "Net-(D2-PadA)") (class "Default")
      (node (ref "D2") (pin "A") (pinfunction "A_A") (pintype "passive"))
      (node (ref "R6") (pin "1") (pinfunction "1_1") (pintype "passive"))
    )
    (net (code "34") (name "Net-(U1-BOOT0)") (class "Default")
      (node (ref "R5") (pin "2") (pinfunction "2_2") (pintype "passive"))
      (node (ref "U1") (pin "94") (pinfunction "BOOT0_94") (pintype "bidirectional"))
    )
    (net (code "35") (name "Net-(U1-PH0-OSC_IN)") (class "Default")
      (node (ref "G1") (pin "1") (pinfunction "1_1") (pintype "passive"))
      (node (ref "U1") (pin "12") (pinfunction "PH0-OSC_IN_12") (pintype "bidirectional"))
    )
    (net (code "36") (name "Net-(U1-PH1-OSC_OUT)") (class "Default")
      (node (ref "G1") (pin "3") (pinfunction "3_3") (pintype "passive"))
      (node (ref "U1") (pin "13") (pinfunction "PH1-OSC_OUT_13") (pintype "bidirectional"))
    )
    (net (code "37") (name "Net-(U1-VCAP_1)") (class "Default")
      (node (ref "C10") (pin "1") (pinfunction "1_1") (pintype "passive"))
      (node (ref "U1") (pin "48") (pinfunction "VCAP_1_48") (pintype "bidirectional"))
    )
    (net (code "38") (name "Net-(U1-VCAP_2)") (class "Default")
      (node (ref "C16") (pin "2") (pinfunction "2_2") (pintype "passive"))
      (node (ref "U1") (pin "73") (pinfunction "VCAP_2_73") (pintype "bidirectional"))
    )
    (net (code "39") (name "Net-(U1-VDDA)") (class "Default")
      (node (ref "C6") (pin "1") (pinfunction "1_1") (pintype "passive"))
      (node (ref "C9") (pin "1") (pinfunction "1_1") (pintype "passive"))
      (node (ref "FB1") (pin "2") (pinfunction "2_2") (pintype "passive"))
      (node (ref "R3") (pin "2") (pinfunction "2_2") (pintype "passive"))
      (node (ref "U1") (pin "22") (pinfunction "VDDA_22") (pintype "bidirectional"))
    )
    (net (code "40") (name "Net-(U1-VREF+)") (class "Default")
      (node (ref "C5") (pin "1") (pinfunction "1_1") (pintype "passive"))
      (node (ref "C8") (pin "1") (pinfunction "1_1") (pintype "passive"))
      (node (ref "R3") (pin "1") (pinfunction "1_1") (pintype "passive"))
      (node (ref "U1") (pin "21") (pinfunction "VREF+_21") (pintype "bidirectional"))
    )
    (net (code "41") (name "Net-(U3-CPH)") (class "Default")
      (node (ref "C24") (pin "1") (pinfunction "1_1") (pintype "passive"))
      (node (ref "U3") (pin "2") (pinfunction "CPH_2") (pintype "power_in"))
    )
    (net (code "42") (name "Net-(U3-CPL)") (class "Default")
      (node (ref "C24") (pin "2") (pinfunction "2_2") (pintype "passive"))
      (node (ref "U3") (pin "1") (pinfunction "CPL_1") (pintype "power_in"))
    )
    (net (code "43") (name "Net-(U3-DVDD)") (class "Default")
      (node (ref "C26") (pin "1") (pinfunction "1_1") (pintype "passive"))
      (node (ref "U3") (pin "33") (pinfunction "DVDD_33") (pintype "power_in"))
    )
    (net (code "44") (name "Net-(U3-VCP)") (class "Default")
      (node (ref "C25") (pin "2") (pinfunction "2_2") (pintype "passive"))
      (node (ref "U3") (pin "3") (pinfunction "VCP_3") (pintype "power_in"))
    )
    (net (code "45") (name "Net-(U4-CB)") (class "Default")
      (node (ref "C28") (pin "2") (pinfunction "2_2") (pintype "passive"))
      (node (ref "U4") (pin "1") (pinfunction "CB_1") (pintype "bidirectional"))
    )
    (net (code "46") (name "Net-(U4-FB)") (class "Default")
      (node (ref "R10") (pin "2") (pinfunction "2_2") (pintype "passive"))
      (node (ref "R9") (pin "1") (pinfunction "1_1") (pintype "passive"))
      (node (ref "U4") (pin "3") (pinfunction "FB_3") (pintype "bidirectional"))
    )
    (net (code "47") (name "Net-(U4-SW)") (class "Default")
      (node (ref "C28") (pin "1") (pinfunction "1_1") (pintype "passive"))
      (node (ref "D3") (pin "C") (pinfunction "C_C") (pintype "passive"))
      (node (ref "L1") (pin "1") (pinfunction "1_1") (pintype "passive"))
      (node (ref "U4") (pin "6") (pinfunction "SW_6") (pintype "bidirectional"))
    )
    (net (code "48") (name "PHASA") (class "Default")
      (node (ref "Q1") (pin "1") (pinfunction "S_1") (pintype "passive"))
      (node (ref "Q1") (pin "2") (pinfunction "S_2") (pintype "passive"))
      (node (ref "Q1") (pin "3") (pinfunction "S_3") (pintype "passive"))
      (node (ref "Q2") (pin "5_1") (pinfunction "D_5_1") (pintype "passive"))
      (node (ref "Q2") (pin "5_10") (pinfunction "D_5_10") (pintype "passive"))
      (node (ref "Q2") (pin "5_11") (pinfunction "D_5_11") (pintype "passive"))
      (node (ref "Q2") (pin "5_12") (pinfunction "D_5_12") (pintype "passive"))
      (node (ref "Q2") (pin "5_13") (pinfunction "D_5_13") (pintype "passive"))
      (node (ref "Q2") (pin "5_14") (pinfunction "D_5_14") (pintype "passive"))
      (node (ref "Q2") (pin "5_15") (pinfunction "D_5_15") (pintype "passive"))
      (node (ref "Q2") (pin "5_16") (pinfunction "D_5_16") (pintype "passive"))
      (node (ref "Q2") (pin "5_17") (pinfunction "D_5_17") (pintype "passive"))
      (node (ref "Q2") (pin "5_18") (pinfunction "D_5_18") (pintype "passive"))
      (node (ref "Q2") (pin "5_19") (pinfunction "D_5_19") (pintype "passive"))
      (node (ref "Q2") (pin "5_2") (pinfunction "D_5_2") (pintype "passive"))
      (node (ref "Q2") (pin "5_20") (pinfunction "D_5_20") (pintype "passive"))
      (node (ref "Q2") (pin "5_21") (pinfunction "D_5_21") (pintype "passive"))
      (node (ref "Q2") (pin "5_22") (pinfunction "D_5_22") (pintype "passive"))
      (node (ref "Q2") (pin "5_23") (pinfunction "D_5_23") (pintype "passive"))
      (node (ref "Q2") (pin "5_24") (pinfunction "D_5_24") (pintype "passive"))
      (node (ref "Q2") (pin "5_25") (pinfunction "D_5_25") (pintype "passive"))
      (node (ref "Q2") (pin "5_26") (pinfunction "D_5_26") (pintype "passive"))
      (node (ref "Q2") (pin "5_27") (pinfunction "D_5_27") (pintype "passive"))
      (node (ref "Q2") (pin "5_28") (pinfunction "D_5_28") (pintype "passive"))
      (node (ref "Q2") (pin "5_29") (pinfunction "D_5_29") (pintype "passive"))
      (node (ref "Q2") (pin "5_3") (pinfunction "D_5_3") (pintype "passive"))
      (node (ref "Q2") (pin "5_30") (pinfunction "D_5_30") (pintype "passive"))
      (node (ref "Q2") (pin "5_4") (pinfunction "D_5_4") (pintype "passive"))
      (node (ref "Q2") (pin "5_5") (pinfunction "D_5_5") (pintype "passive"))
      (node (ref "Q2") (pin "5_6") (pinfunction "D_5_6") (pintype "passive"))
      (node (ref "Q2") (pin "5_7") (pinfunction "D_5_7") (pintype "passive"))
      (node (ref "Q2") (pin "5_8") (pinfunction "D_5_8") (pintype "passive"))
      (node (ref "Q2") (pin "5_9") (pinfunction "D_5_9") (pintype "passive"))
      (node (ref "U3") (pin "7") (pinfunction "SHA_7") (pintype "input"))
      (node (ref "X4") (pin "1") (pinfunction "1_1") (pintype "bidirectional"))
    )
    (net (code "49") (name "PHASB") (class "Default")
      (node (ref "Q3") (pin "1") (pinfunction "S_1") (pintype "passive"))
      (node (ref "Q3") (pin "2") (pinfunction "S_2") (pintype "passive"))
      (node (ref "Q3") (pin "3") (pinfunction "S_3") (pintype "passive"))
      (node (ref "Q4") (pin "5_1") (pinfunction "D_5_1") (pintype "passive"))
      (node (ref "Q4") (pin "5_10") (pinfunction "D_5_10") (pintype "passive"))
      (node (ref "Q4") (pin "5_11") (pinfunction "D_5_11") (pintype "passive"))
      (node (ref "Q4") (pin "5_12") (pinfunction "D_5_12") (pintype "passive"))
      (node (ref "Q4") (pin "5_13") (pinfunction "D_5_13") (pintype "passive"))
      (node (ref "Q4") (pin "5_14") (pinfunction "D_5_14") (pintype "passive"))
      (node (ref "Q4") (pin "5_15") (pinfunction "D_5_15") (pintype "passive"))
      (node (ref "Q4") (pin "5_16") (pinfunction "D_5_16") (pintype "passive"))
      (node (ref "Q4") (pin "5_17") (pinfunction "D_5_17") (pintype "passive"))
      (node (ref "Q4") (pin "5_18") (pinfunction "D_5_18") (pintype "passive"))
      (node (ref "Q4") (pin "5_19") (pinfunction "D_5_19") (pintype "passive"))
      (node (ref "Q4") (pin "5_2") (pinfunction "D_5_2") (pintype "passive"))
      (node (ref "Q4") (pin "5_20") (pinfunction "D_5_20") (pintype "passive"))
      (node (ref "Q4") (pin "5_21") (pinfunction "D_5_21") (pintype "passive"))
      (node (ref "Q4") (pin "5_22") (pinfunction "D_5_22") (pintype "passive"))
      (node (ref "Q4") (pin "5_23") (pinfunction "D_5_23") (pintype "passive"))
      (node (ref "Q4") (pin "5_24") (pinfunction "D_5_24") (pintype "passive"))
      (node (ref "Q4") (pin "5_25") (pinfunction "D_5_25") (pintype "passive"))
      (node (ref "Q4") (pin "5_26") (pinfunction "D_5_26") (pintype "passive"))
      (node (ref "Q4") (pin "5_27") (pinfunction "D_5_27") (pintype "passive"))
      (node (ref "Q4") (pin "5_28") (pinfunction "D_5_28") (pintype "passive"))
      (node (ref "Q4") (pin "5_29") (pinfunction "D_5_29") (pintype "passive"))
      (node (ref "Q4") (pin "5_3") (pinfunction "D_5_3") (pintype "passive"))
      (node (ref "Q4") (pin "5_30") (pinfunction "D_5_30") (pintype "passive"))
      (node (ref "Q4") (pin "5_4") (pinfunction "D_5_4") (pintype "passive"))
      (node (ref "Q4") (pin "5_5") (pinfunction "D_5_5") (pintype "passive"))
      (node (ref "Q4") (pin "5_6") (pinfunction "D_5_6") (pintype "passive"))
      (node (ref "Q4") (pin "5_7") (pinfunction "D_5_7") (pintype "passive"))
      (node (ref "Q4") (pin "5_8") (pinfunction "D_5_8") (pintype "passive"))
      (node (ref "Q4") (pin "5_9") (pinfunction "D_5_9") (pintype "passive"))
      (node (ref "U3") (pin "14") (pinfunction "SHB_14") (pintype "input"))
      (node (ref "X5") (pin "1") (pinfunction "1_1") (pintype "bidirectional"))
    )
    (net (code "50") (name "PHASC") (class "Default")
      (node (ref "Q5") (pin "1") (pinfunction "S_1") (pintype "passive"))
      (node (ref "Q5") (pin "2") (pinfunction "S_2") (pintype "passive"))
      (node (ref "Q5") (pin "3") (pinfunction "S_3") (pintype "passive"))
      (node (ref "Q6") (pin "5_1") (pinfunction "D_5_1") (pintype "passive"))
      (node (ref "Q6") (pin "5_10") (pinfunction "D_5_10") (pintype "passive"))
      (node (ref "Q6") (pin "5_11") (pinfunction "D_5_11") (pintype "passive"))
      (node (ref "Q6") (pin "5_12") (pinfunction "D_5_12") (pintype "passive"))
      (node (ref "Q6") (pin "5_13") (pinfunction "D_5_13") (pintype "passive"))
      (node (ref "Q6") (pin "5_14") (pinfunction "D_5_14") (pintype "passive"))
      (node (ref "Q6") (pin "5_15") (pinfunction "D_5_15") (pintype "passive"))
      (node (ref "Q6") (pin "5_16") (pinfunction "D_5_16") (pintype "passive"))
      (node (ref "Q6") (pin "5_17") (pinfunction "D_5_17") (pintype "passive"))
      (node (ref "Q6") (pin "5_18") (pinfunction "D_5_18") (pintype "passive"))
      (node (ref "Q6") (pin "5_19") (pinfunction "D_5_19") (pintype "passive"))
      (node (ref "Q6") (pin "5_2") (pinfunction "D_5_2") (pintype "passive"))
      (node (ref "Q6") (pin "5_20") (pinfunction "D_5_20") (pintype "passive"))
      (node (ref "Q6") (pin "5_21") (pinfunction "D_5_21") (pintype "passive"))
      (node (ref "Q6") (pin "5_22") (pinfunction "D_5_22") (pintype "passive"))
      (node (ref "Q6") (pin "5_23") (pinfunction "D_5_23") (pintype "passive"))
      (node (ref "Q6") (pin "5_24") (pinfunction "D_5_24") (pintype "passive"))
      (node (ref "Q6") (pin "5_25") (pinfunction "D_5_25") (pintype "passive"))
      (node (ref "Q6") (pin "5_26") (pinfunction "D_5_26") (pintype "passive"))
      (node (ref "Q6") (pin "5_27") (pinfunction "D_5_27") (pintype "passive"))
      (node (ref "Q6") (pin "5_28") (pinfunction "D_5_28") (pintype "passive"))
      (node (ref "Q6") (pin "5_29") (pinfunction "D_5_29") (pintype "passive"))
      (node (ref "Q6") (pin "5_3") (pinfunction "D_5_3") (pintype "passive"))
      (node (ref "Q6") (pin "5_30") (pinfunction "D_5_30") (pintype "passive"))
      (node (ref "Q6") (pin "5_4") (pinfunction "D_5_4") (pintype "passive"))
      (node (ref "Q6") (pin "5_5") (pinfunction "D_5_5") (pintype "passive"))
      (node (ref "Q6") (pin "5_6") (pinfunction "D_5_6") (pintype "passive"))
      (node (ref "Q6") (pin "5_7") (pinfunction "D_5_7") (pintype "passive"))
      (node (ref "Q6") (pin "5_8") (pinfunction "D_5_8") (pintype "passive"))
      (node (ref "Q6") (pin "5_9") (pinfunction "D_5_9") (pintype "passive"))
      (node (ref "U3") (pin "17") (pinfunction "SHC_17") (pintype "input"))
      (node (ref "X6") (pin "1") (pinfunction "1_1") (pintype "bidirectional"))
    )
    (net (code "51") (name "PWMA") (class "Default")
      (node (ref "U1") (pin "69") (pinfunction "PA10_69") (pintype "bidirectional"))
      (node (ref "U3") (pin "38") (pinfunction "INHC_38") (pintype "input"))
    )
    (net (code "52") (name "PWMB") (class "Default")
      (node (ref "U1") (pin "68") (pinfunction "PA9_68") (pintype "bidirectional"))
      (node (ref "U3") (pin "36") (pinfunction "INHB_36") (pintype "input"))
    )
    (net (code "53") (name "PWMC") (class "Default")
      (node (ref "U1") (pin "67") (pinfunction "PA8_67") (pintype "bidirectional"))
      (node (ref "U3") (pin "34") (pinfunction "INHA_34") (pintype "input"))
    )
    (net (code "54") (name "SPA") (class "Default")
      (node (ref "Q2") (pin "1") (pinfunction "S_1") (pintype "passive"))
      (node (ref "Q2") (pin "2") (pinfunction "S_2") (pintype "passive"))
      (node (ref "Q2") (pin "3") (pinfunction "S_3") (pintype "passive"))
      (node (ref "R11") (pin "2") (pinfunction "2_2") (pintype "passive"))
      (node (ref "U3") (pin "9") (pinfunction "SPA_9") (pintype "input"))
    )
    (net (code "55") (name "SPB") (class "Default")
      (node (ref "Q4") (pin "1") (pinfunction "S_1") (pintype "passive"))
      (node (ref "Q4") (pin "2") (pinfunction "S_2") (pintype "passive"))
      (node (ref "Q4") (pin "3") (pinfunction "S_3") (pintype "passive"))
      (node (ref "R12") (pin "2") (pinfunction "2_2") (pintype "passive"))
      (node (ref "U3") (pin "12") (pinfunction "SPB_12") (pintype "input"))
    )
    (net (code "56") (name "SPI-MISO") (class "Default")
      (node (ref "R8") (pin "1") (pinfunction "1_1") (pintype "passive"))
      (node (ref "U1") (pin "31") (pinfunction "PA6/SPI1_MISO_31") (pintype "bidirectional"))
      (node (ref "U3") (pin "26") (pinfunction "SDO_26") (pintype "output"))
    )
    (net (code "57") (name "SPI-MOSI") (class "Default")
      (node (ref "U1") (pin "32") (pinfunction "PA7/SPI1_MOSI_32") (pintype "bidirectional"))
      (node (ref "U3") (pin "27") (pinfunction "SDI_27") (pintype "input"))
    )
    (net (code "58") (name "SPI-NSS-DRV") (class "Default")
      (node (ref "U1") (pin "29") (pinfunction "PA4/SPI1_NSS_29") (pintype "bidirectional"))
      (node (ref "U3") (pin "29") (pinfunction "NSCS_29") (pintype "input"))
    )
    (net (code "59") (name "SPI-SCK") (class "Default")
      (node (ref "U1") (pin "30") (pinfunction "PA5/SPI1_SCK_30") (pintype "bidirectional"))
      (node (ref "U3") (pin "28") (pinfunction "SCLK_28") (pintype "input"))
    )
    (net (code "60") (name "unconnected-(U1-PA1-Pad24)") (class "Default")
      (node (ref "U1") (pin "24") (pinfunction "PA1_24") (pintype "bidirectional"))
    )
    (net (code "61") (name "unconnected-(U1-PA12-Pad71)") (class "Default")
      (node (ref "U1") (pin "71") (pinfunction "PA12_71") (pintype "bidirectional"))
    )
    (net (code "62") (name "unconnected-(U1-PB0-Pad35)") (class "Default")
      (node (ref "U1") (pin "35") (pinfunction "PB0_35") (pintype "bidirectional"))
    )
    (net (code "63") (name "unconnected-(U1-PB1-Pad36)") (class "Default")
      (node (ref "U1") (pin "36") (pinfunction "PB1_36") (pintype "bidirectional"))
    )
    (net (code "64") (name "unconnected-(U1-PB2-Pad37)") (class "Default")
      (node (ref "U1") (pin "37") (pinfunction "PB2_37") (pintype "bidirectional"))
    )
    (net (code "65") (name "unconnected-(U1-PB3-Pad89)") (class "Default")
      (node (ref "U1") (pin "89") (pinfunction "PB3_89") (pintype "bidirectional"))
    )
    (net (code "66") (name "unconnected-(U1-PB4-Pad90)") (class "Default")
      (node (ref "U1") (pin "90") (pinfunction "PB4_90") (pintype "bidirectional"))
    )
    (net (code "67") (name "unconnected-(U1-PB5{slash}CAN2_RX-Pad91)") (class "Default")
      (node (ref "U1") (pin "91") (pinfunction "PB5/CAN2_RX_91") (pintype "bidirectional"))
    )
    (net (code "68") (name "unconnected-(U1-PB10-Pad47)") (class "Default")
      (node (ref "U1") (pin "47") (pinfunction "PB10_47") (pintype "bidirectional"))
    )
    (net (code "69") (name "unconnected-(U1-PB12-Pad51)") (class "Default")
      (node (ref "U1") (pin "51") (pinfunction "PB12_51") (pintype "bidirectional"))
    )
    (net (code "70") (name "unconnected-(U1-PB13-Pad52)") (class "Default")
      (node (ref "U1") (pin "52") (pinfunction "PB13_52") (pintype "bidirectional"))
    )
    (net (code "71") (name "unconnected-(U1-PB14-Pad53)") (class "Default")
      (node (ref "U1") (pin "53") (pinfunction "PB14_53") (pintype "bidirectional"))
    )
    (net (code "72") (name "unconnected-(U1-PB15-Pad54)") (class "Default")
      (node (ref "U1") (pin "54") (pinfunction "PB15_54") (pintype "bidirectional"))
    )
    (net (code "73") (name "unconnected-(U1-PC2-Pad17)") (class "Default")
      (node (ref "U1") (pin "17") (pinfunction "PC2_17") (pintype "bidirectional"))
    )
    (net (code "74") (name "unconnected-(U1-PC3-Pad18)") (class "Default")
      (node (ref "U1") (pin "18") (pinfunction "PC3_18") (pintype "bidirectional"))
    )
    (net (code "75") (name "unconnected-(U1-PC4-Pad33)") (class "Default")
      (node (ref "U1") (pin "33") (pinfunction "PC4_33") (pintype "bidirectional"))
    )
    (net (code "76") (name "unconnected-(U1-PC6-Pad63)") (class "Default")
      (node (ref "U1") (pin "63") (pinfunction "PC6_63") (pintype "bidirectional"))
    )
    (net (code "77") (name "unconnected-(U1-PC7-Pad64)") (class "Default")
      (node (ref "U1") (pin "64") (pinfunction "PC7_64") (pintype "bidirectional"))
    )
    (net (code "78") (name "unconnected-(U1-PC8-Pad65)") (class "Default")
      (node (ref "U1") (pin "65") (pinfunction "PC8_65") (pintype "bidirectional"))
    )
    (net (code "79") (name "unconnected-(U1-PC9-Pad66)") (class "Default")
      (node (ref "U1") (pin "66") (pinfunction "PC9_66") (pintype "bidirectional"))
    )
    (net (code "80") (name "unconnected-(U1-PC13-Pad7)") (class "Default")
      (node (ref "U1") (pin "7") (pinfunction "PC13_7") (pintype "bidirectional"))
    )
    (net (code "81") (name "unconnected-(U1-PC14-OSC32_IN-Pad8)") (class "Default")
      (node (ref "U1") (pin "8") (pinfunction "PC14-OSC32_IN_8") (pintype "bidirectional"))
    )
    (net (code "82") (name "unconnected-(U1-PC15-OSC32_OUT-Pad9)") (class "Default")
      (node (ref "U1") (pin "9") (pinfunction "PC15-OSC32_OUT_9") (pintype "bidirectional"))
    )
    (net (code "83") (name "unconnected-(U1-PD0-Pad81)") (class "Default")
      (node (ref "U1") (pin "81") (pinfunction "PD0_81") (pintype "bidirectional"))
    )
    (net (code "84") (name "unconnected-(U1-PD1-Pad82)") (class "Default")
      (node (ref "U1") (pin "82") (pinfunction "PD1_82") (pintype "bidirectional"))
    )
    (net (code "85") (name "unconnected-(U1-PD2-Pad83)") (class "Default")
      (node (ref "U1") (pin "83") (pinfunction "PD2_83") (pintype "bidirectional"))
    )
    (net (code "86") (name "unconnected-(U1-PD3-Pad84)") (class "Default")
      (node (ref "U1") (pin "84") (pinfunction "PD3_84") (pintype "bidirectional"))
    )
    (net (code "87") (name "unconnected-(U1-PD4-Pad85)") (class "Default")
      (node (ref "U1") (pin "85") (pinfunction "PD4_85") (pintype "bidirectional"))
    )
    (net (code "88") (name "unconnected-(U1-PD5-Pad86)") (class "Default")
      (node (ref "U1") (pin "86") (pinfunction "PD5_86") (pintype "bidirectional"))
    )
    (net (code "89") (name "unconnected-(U1-PD6-Pad87)") (class "Default")
      (node (ref "U1") (pin "87") (pinfunction "PD6_87") (pintype "bidirectional"))
    )
    (net (code "90") (name "unconnected-(U1-PD7-Pad88)") (class "Default")
      (node (ref "U1") (pin "88") (pinfunction "PD7_88") (pintype "bidirectional"))
    )
    (net (code "91") (name "unconnected-(U1-PD8-Pad55)") (class "Default")
      (node (ref "U1") (pin "55") (pinfunction "PD8_55") (pintype "bidirectional"))
    )
    (net (code "92") (name "unconnected-(U1-PD9-Pad56)") (class "Default")
      (node (ref "U1") (pin "56") (pinfunction "PD9_56") (pintype "bidirectional"))
    )
    (net (code "93") (name "unconnected-(U1-PD10-Pad57)") (class "Default")
      (node (ref "U1") (pin "57") (pinfunction "PD10_57") (pintype "bidirectional"))
    )
    (net (code "94") (name "unconnected-(U1-PD11-Pad58)") (class "Default")
      (node (ref "U1") (pin "58") (pinfunction "PD11_58") (pintype "bidirectional"))
    )
    (net (code "95") (name "unconnected-(U1-PD12-Pad59)") (class "Default")
      (node (ref "U1") (pin "59") (pinfunction "PD12_59") (pintype "bidirectional"))
    )
    (net (code "96") (name "unconnected-(U1-PD13-Pad60)") (class "Default")
      (node (ref "U1") (pin "60") (pinfunction "PD13_60") (pintype "bidirectional"))
    )
    (net (code "97") (name "unconnected-(U1-PD14-Pad61)") (class "Default")
      (node (ref "U1") (pin "61") (pinfunction "PD14_61") (pintype "bidirectional"))
    )
    (net (code "98") (name "unconnected-(U1-PD15-Pad62)") (class "Default")
      (node (ref "U1") (pin "62") (pinfunction "PD15_62") (pintype "bidirectional"))
    )
    (net (code "99") (name "unconnected-(U1-PE0-Pad97)") (class "Default")
      (node (ref "U1") (pin "97") (pinfunction "PE0_97") (pintype "bidirectional"))
    )
    (net (code "100") (name "unconnected-(U1-PE1-Pad98)") (class "Default")
      (node (ref "U1") (pin "98") (pinfunction "PE1_98") (pintype "bidirectional"))
    )
    (net (code "101") (name "unconnected-(U1-PE2-Pad1)") (class "Default")
      (node (ref "U1") (pin "1") (pinfunction "PE2_1") (pintype "bidirectional"))
    )
    (net (code "102") (name "unconnected-(U1-PE3-Pad2)") (class "Default")
      (node (ref "U1") (pin "2") (pinfunction "PE3_2") (pintype "bidirectional"))
    )
    (net (code "103") (name "unconnected-(U1-PE4-Pad3)") (class "Default")
      (node (ref "U1") (pin "3") (pinfunction "PE4_3") (pintype "bidirectional"))
    )
    (net (code "104") (name "unconnected-(U1-PE5-Pad4)") (class "Default")
      (node (ref "U1") (pin "4") (pinfunction "PE5_4") (pintype "bidirectional"))
    )
    (net (code "105") (name "unconnected-(U1-PE6-Pad5)") (class "Default")
      (node (ref "U1") (pin "5") (pinfunction "PE6_5") (pintype "bidirectional"))
    )
    (net (code "106") (name "unconnected-(U1-PE7-Pad38)") (class "Default")
      (node (ref "U1") (pin "38") (pinfunction "PE7_38") (pintype "bidirectional"))
    )
    (net (code "107") (name "unconnected-(U1-PE8-Pad39)") (class "Default")
      (node (ref "U1") (pin "39") (pinfunction "PE8_39") (pintype "bidirectional"))
    )
    (net (code "108") (name "unconnected-(U1-PE9-Pad40)") (class "Default")
      (node (ref "U1") (pin "40") (pinfunction "PE9_40") (pintype "bidirectional"))
    )
    (net (code "109") (name "unconnected-(U1-PE10-Pad41)") (class "Default")
      (node (ref "U1") (pin "41") (pinfunction "PE10_41") (pintype "bidirectional"))
    )
    (net (code "110") (name "unconnected-(U1-PE11-Pad42)") (class "Default")
      (node (ref "U1") (pin "42") (pinfunction "PE11_42") (pintype "bidirectional"))
    )
    (net (code "111") (name "unconnected-(U1-PE12-Pad43)") (class "Default")
      (node (ref "U1") (pin "43") (pinfunction "PE12_43") (pintype "bidirectional"))
    )
    (net (code "112") (name "unconnected-(U1-PE13-Pad44)") (class "Default")
      (node (ref "U1") (pin "44") (pinfunction "PE13_44") (pintype "bidirectional"))
    )
    (net (code "113") (name "unconnected-(U1-PE14-Pad45)") (class "Default")
      (node (ref "U1") (pin "45") (pinfunction "PE14_45") (pintype "bidirectional"))
    )
    (net (code "114") (name "unconnected-(U1-PE15-Pad46)") (class "Default")
      (node (ref "U1") (pin "46") (pinfunction "PE15_46") (pintype "bidirectional"))
    )
    (net (code "115") (name "unconnected-(U3-CAL-Pad31)") (class "Default")
      (node (ref "U3") (pin "31") (pinfunction "CAL_31") (pintype "input"))
    )
    (net (code "116") (name "unconnected-(U3-SOC-Pad21)") (class "Default")
      (node (ref "U3") (pin "21") (pinfunction "SOC_21") (pintype "output"))
    )
    (net (code "117") (name "unconnected-(U4-SHDN-Pad4)") (class "Default")
      (node (ref "U4") (pin "4") (pinfunction "SHDN_4") (pintype "bidirectional"))
    )
    (net (code "118") (name "unconnected-(U5-PG-Pad3)") (class "Default")
      (node (ref "U5") (pin "3") (pinfunction "PG_3") (pintype "bidirectional"))
    )
    (net (code "119") (name "unconnected-(U6-A-Pad6)") (class "Default")
      (node (ref "U6") (pin "6") (pinfunction "A_6") (pintype "bidirectional"))
    )
    (net (code "120") (name "unconnected-(U6-B-Pad2)") (class "Default")
      (node (ref "U6") (pin "2") (pinfunction "B_2") (pintype "bidirectional"))
    )
    (net (code "121") (name "unconnected-(U6-NC1-Pad1)") (class "Default")
      (node (ref "U6") (pin "1") (pinfunction "NC1_1") (pintype "bidirectional"))
    )
    (net (code "122") (name "unconnected-(U6-NC2-Pad9)") (class "Default")
      (node (ref "U6") (pin "9") (pinfunction "NC2_9") (pintype "bidirectional"))
    )
    (net (code "123") (name "unconnected-(U6-NC3-Pad10)") (class "Default")
      (node (ref "U6") (pin "10") (pinfunction "NC3_10") (pintype "bidirectional"))
    )
    (net (code "124") (name "unconnected-(U6-NC4-Pad11)") (class "Default")
      (node (ref "U6") (pin "11") (pinfunction "NC4_11") (pintype "bidirectional"))
    )
    (net (code "125") (name "unconnected-(U6-NC5-Pad14)") (class "Default")
      (node (ref "U6") (pin "14") (pinfunction "NC5_14") (pintype "bidirectional"))
    )
    (net (code "126") (name "unconnected-(U6-NC6-Pad15)") (class "Default")
      (node (ref "U6") (pin "15") (pinfunction "NC6_15") (pintype "bidirectional"))
    )
    (net (code "127") (name "unconnected-(U6-VFLASH-Pad16)") (class "Default")
      (node (ref "U6") (pin "16") (pinfunction "VFLASH_16") (pintype "bidirectional"))
    )
    (net (code "128") (name "unconnected-(U6-Z-Pad3)") (class "Default")
      (node (ref "U6") (pin "3") (pinfunction "Z_3") (pintype "bidirectional"))
    )
  )
)
